# Project-PCB.net
KiCad netlist of a schematic drawn in Altium Designer
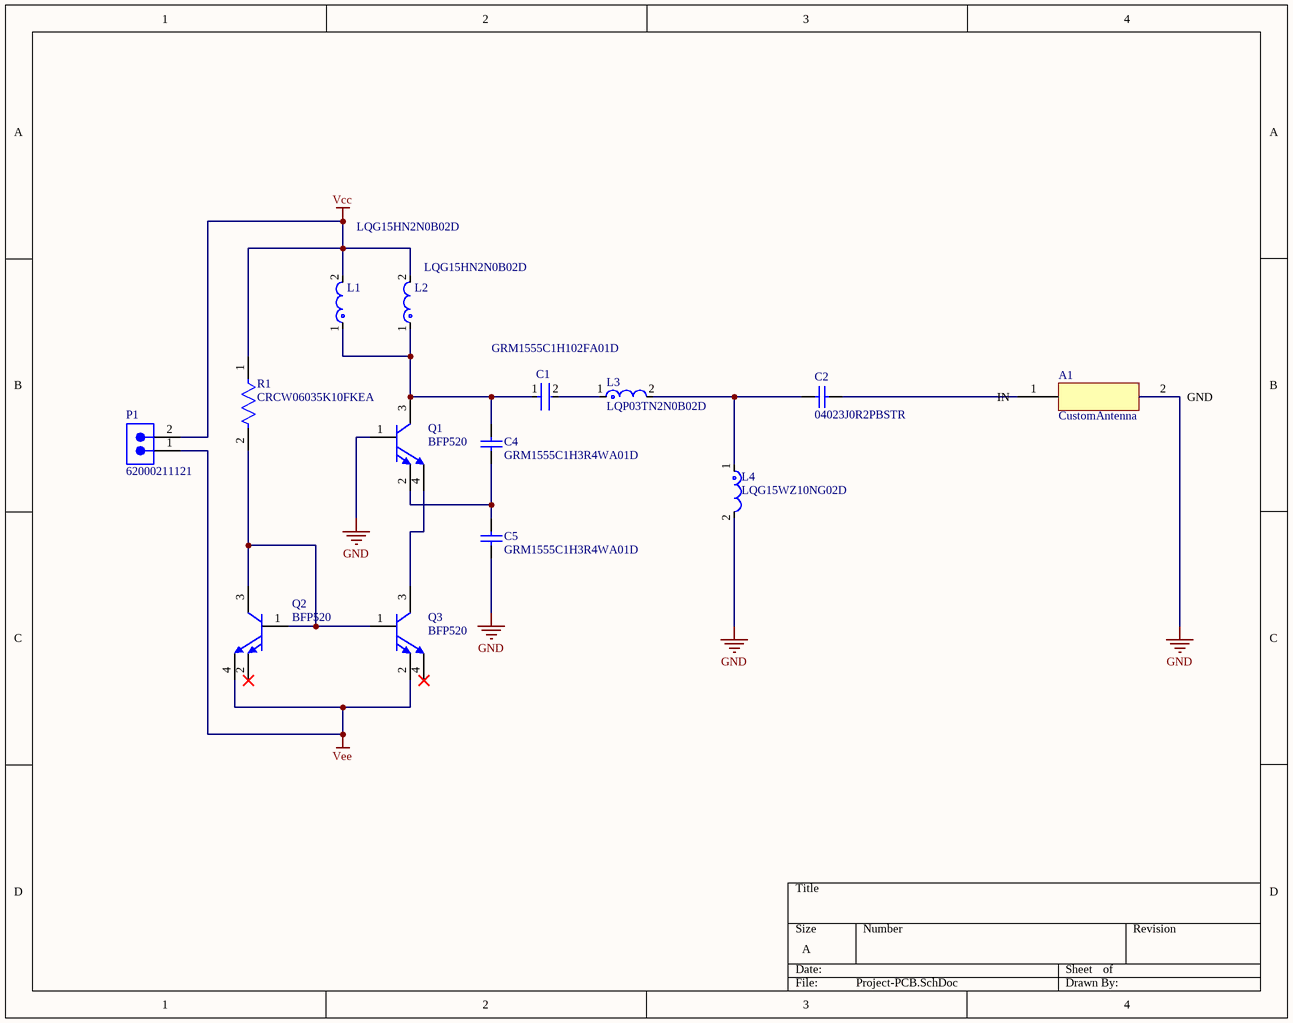
[diagram p0: Project-PCB.SchDoc]

(export (version "E")
  (design (tool "Eeschema 10.0.6"))
  (components
    (comp (ref "A1")
      (value "CustomAntenna")
      (footprint "CustomAntennaFootprint")
      (description "Custom Antenna from CST")
      (libsource (lib "AntennaLib") (part "CustomAntenna"))
    )
    (comp (ref "C1")
      (value "GRM1555C1H102FA01D")
      (footprint "FP-GRM155-0_05-IPC_B")
      (description "Chip Multilayer Ceramic Capacitors for General Purpose, 0402, 1000pF, C0G, 30ppm/°C, 1%, 50V")
      (fields (field (name "TOLERANCE") "1%") (field (name "VOLTAGE") "50V"))
      (libsource (lib "Altium Content Vault") (part "02cd4be3c70576c341d710602a673aa"))
    )
    (comp (ref "C2")
      (value "04023J0R2PBSTR")
      (footprint "CAPC1006X50X20LL10T10")
      (fields (field (name "MANUFACTURER") "AVX Interconnect / Elco"))
      (libsource (lib "Altium Content Vault") (part "CAP"))
    )
    (comp (ref "C4")
      (value "GRM1555C1H3R4WA01D")
      (footprint "CAPC1005X55X25ML05T10")
      (fields (field (name "MANUFACTURER") "Murata"))
      (libsource (lib "Altium Content Vault") (part "CAP"))
    )
    (comp (ref "C5")
      (value "GRM1555C1H3R4WA01D")
      (footprint "CAPC1005X55X25ML05T10")
      (fields (field (name "MANUFACTURER") "Murata"))
      (libsource (lib "Altium Content Vault") (part "CAP"))
    )
    (comp (ref "L1")
      (value "LQG15HN2N0B02D")
      (footprint "FP-LQG15HH_02-MFG")
      (description "Multilayer type RF Inductor 2nH ±0.1nH 0.09Ω 900mA 0402")
      (libsource (lib "Altium Content Vault") (part "4cc4b267dca4c8e51f7102f422741d8"))
    )
    (comp (ref "L2")
      (value "LQG15HN2N0B02D")
      (footprint "FP-LQG15HH_02-MFG")
      (description "Multilayer type RF Inductor 2nH ±0.1nH 0.09Ω 900mA 0402")
      (libsource (lib "Altium Content Vault") (part "4cc4b267dca4c8e51f7102f422741d8"))
    )
    (comp (ref "L3")
      (value "LQP03TN2N0B02D")
      (footprint "FP-LQP03TG_02-IPC_A")
      (description "Film type RF Inductor 2nH ±0.1nH 600mA 0.15Ω 0201 (0603)")
      (libsource (lib "Altium Content Vault") (part "4cc4b267dca4c8e51f7102f422741d8"))
    )
    (comp (ref "L4")
      (value "LQG15WZ10NG02D")
      (footprint "FP-LQG15WH_02-IPC_A")
      (description "Multilayer type Inductor for Automotive 10nH ±2% 0.19Ω 500mA 0402")
      (libsource (lib "Altium Content Vault") (part "4cc4b267dca4c8e51f7102f422741d8"))
    )
    (comp (ref "P1")
      (value "62000211121")
      (footprint "62000211121")
      (libsource (lib "Altium Content Vault") (part "Header_Male_1R_02P"))
    )
    (comp (ref "Q1")
      (value "BFP520")
      (footprint "INF-SOT343_V")
      (description "NPN Silicon RF Transistor, 2.5 V VCEO, 40 mA IC, 23.5 dB Gmax, SOT343, Green")
      (fields (field (name "MANUFACTURER") "Infineon"))
      (libsource (lib "Altium Content Vault") (part "INF-BFP520-4"))
    )
    (comp (ref "Q2")
      (value "BFP520")
      (footprint "INF-SOT343_V")
      (description "NPN Silicon RF Transistor, 2.5 V VCEO, 40 mA IC, 23.5 dB Gmax, SOT343, Green")
      (fields (field (name "MANUFACTURER") "Infineon"))
      (libsource (lib "Altium Content Vault") (part "INF-BFP520-4"))
    )
    (comp (ref "Q3")
      (value "BFP520")
      (footprint "INF-SOT343_V")
      (description "NPN Silicon RF Transistor, 2.5 V VCEO, 40 mA IC, 23.5 dB Gmax, SOT343, Green")
      (fields (field (name "MANUFACTURER") "Infineon"))
      (libsource (lib "Altium Content Vault") (part "INF-BFP520-4"))
    )
    (comp (ref "R1")
      (value "CRCW06035K10FKEA")
      (footprint "FP-CRCW0603-e3-IPC_C")
      (description "RES Thick Film, 5.1kΩ, 1%, 0.1W, 100ppm/°C, 0603")
      (fields (field (name "TOLERANCE") "1%"))
      (libsource (lib "Altium Content Vault") (part "1029c3af85768c4190bb7ad29bc67b5"))
    )
  )
  (nets
    (net (code "1") (name "GND") (class "Default")
      (node (ref "A1") (pin "2") (pinfunction "GND_2") (pintype "passive"))
      (node (ref "C5") (pin "1") (pinfunction "1_1") (pintype "passive"))
      (node (ref "L4") (pin "2") (pinfunction "2_2") (pintype "passive"))
      (node (ref "Q1") (pin "1") (pinfunction "B_1") (pintype "passive"))
    )
    (net (code "2") (name "Net-(A1-IN)") (class "Default")
      (node (ref "A1") (pin "1") (pinfunction "IN_1") (pintype "passive"))
      (node (ref "C2") (pin "2") (pinfunction "2_2") (pintype "passive"))
    )
    (net (code "3") (name "Net-(C1-Pad2)") (class "Default")
      (node (ref "C1") (pin "2") (pinfunction "2_2") (pintype "passive"))
      (node (ref "L3") (pin "1") (pinfunction "1_1") (pintype "passive"))
    )
    (net (code "4") (name "Net-(C2-Pad1)") (class "Default")
      (node (ref "C2") (pin "1") (pinfunction "1_1") (pintype "passive"))
      (node (ref "L3") (pin "2") (pinfunction "2_2") (pintype "passive"))
      (node (ref "L4") (pin "1") (pinfunction "1_1") (pintype "passive"))
    )
    (net (code "5") (name "Net-(C4-Pad1)") (class "Default")
      (node (ref "C4") (pin "1") (pinfunction "1_1") (pintype "passive"))
      (node (ref "C5") (pin "2") (pinfunction "2_2") (pintype "passive"))
      (node (ref "Q1") (pin "2") (pinfunction "E_2") (pintype "passive"))
    )
    (net (code "6") (name "Net-(Q1-C)") (class "Default")
      (node (ref "C1") (pin "1") (pinfunction "1_1") (pintype "passive"))
      (node (ref "C4") (pin "2") (pinfunction "2_2") (pintype "passive"))
      (node (ref "L1") (pin "1") (pinfunction "1_1") (pintype "passive"))
      (node (ref "L2") (pin "1") (pinfunction "1_1") (pintype "passive"))
      (node (ref "Q1") (pin "3") (pinfunction "C_3") (pintype "passive"))
    )
    (net (code "7") (name "Net-(Q2-B)") (class "Default")
      (node (ref "Q2") (pin "1") (pinfunction "B_1") (pintype "passive"))
      (node (ref "Q2") (pin "3") (pinfunction "C_3") (pintype "passive"))
      (node (ref "Q3") (pin "1") (pinfunction "B_1") (pintype "passive"))
      (node (ref "R1") (pin "2") (pinfunction "2_2") (pintype "passive"))
    )
    (net (code "8") (name "Net-(Q3-C)") (class "Default")
      (node (ref "Q1") (pin "4") (pinfunction "E_4") (pintype "passive"))
      (node (ref "Q3") (pin "3") (pinfunction "C_3") (pintype "passive"))
    )
    (net (code "9") (name "Vcc") (class "Default")
      (node (ref "L1") (pin "2") (pinfunction "2_2") (pintype "passive"))
      (node (ref "L2") (pin "2") (pinfunction "2_2") (pintype "passive"))
      (node (ref "P1") (pin "2") (pinfunction "2_2") (pintype "passive"))
      (node (ref "R1") (pin "1") (pinfunction "1_1") (pintype "passive"))
    )
    (net (code "10") (name "Vee") (class "Default")
      (node (ref "P1") (pin "1") (pinfunction "1_1") (pintype "passive"))
      (node (ref "Q2") (pin "4") (pinfunction "E_4") (pintype "passive"))
      (node (ref "Q3") (pin "2") (pinfunction "E_2") (pintype "passive"))
    )
    (net (code "11") (name "unconnected-(Q2-E-Pad2)") (class "Default")
      (node (ref "Q2") (pin "2") (pinfunction "E_2") (pintype "passive+no_connect"))
    )
    (net (code "12") (name "unconnected-(Q3-E-Pad4)") (class "Default")
      (node (ref "Q3") (pin "4") (pinfunction "E_4") (pintype "passive+no_connect"))
    )
  )
)
